# CONNECTOR_A.net
KiCad netlist of a schematic drawn in Altium Designer
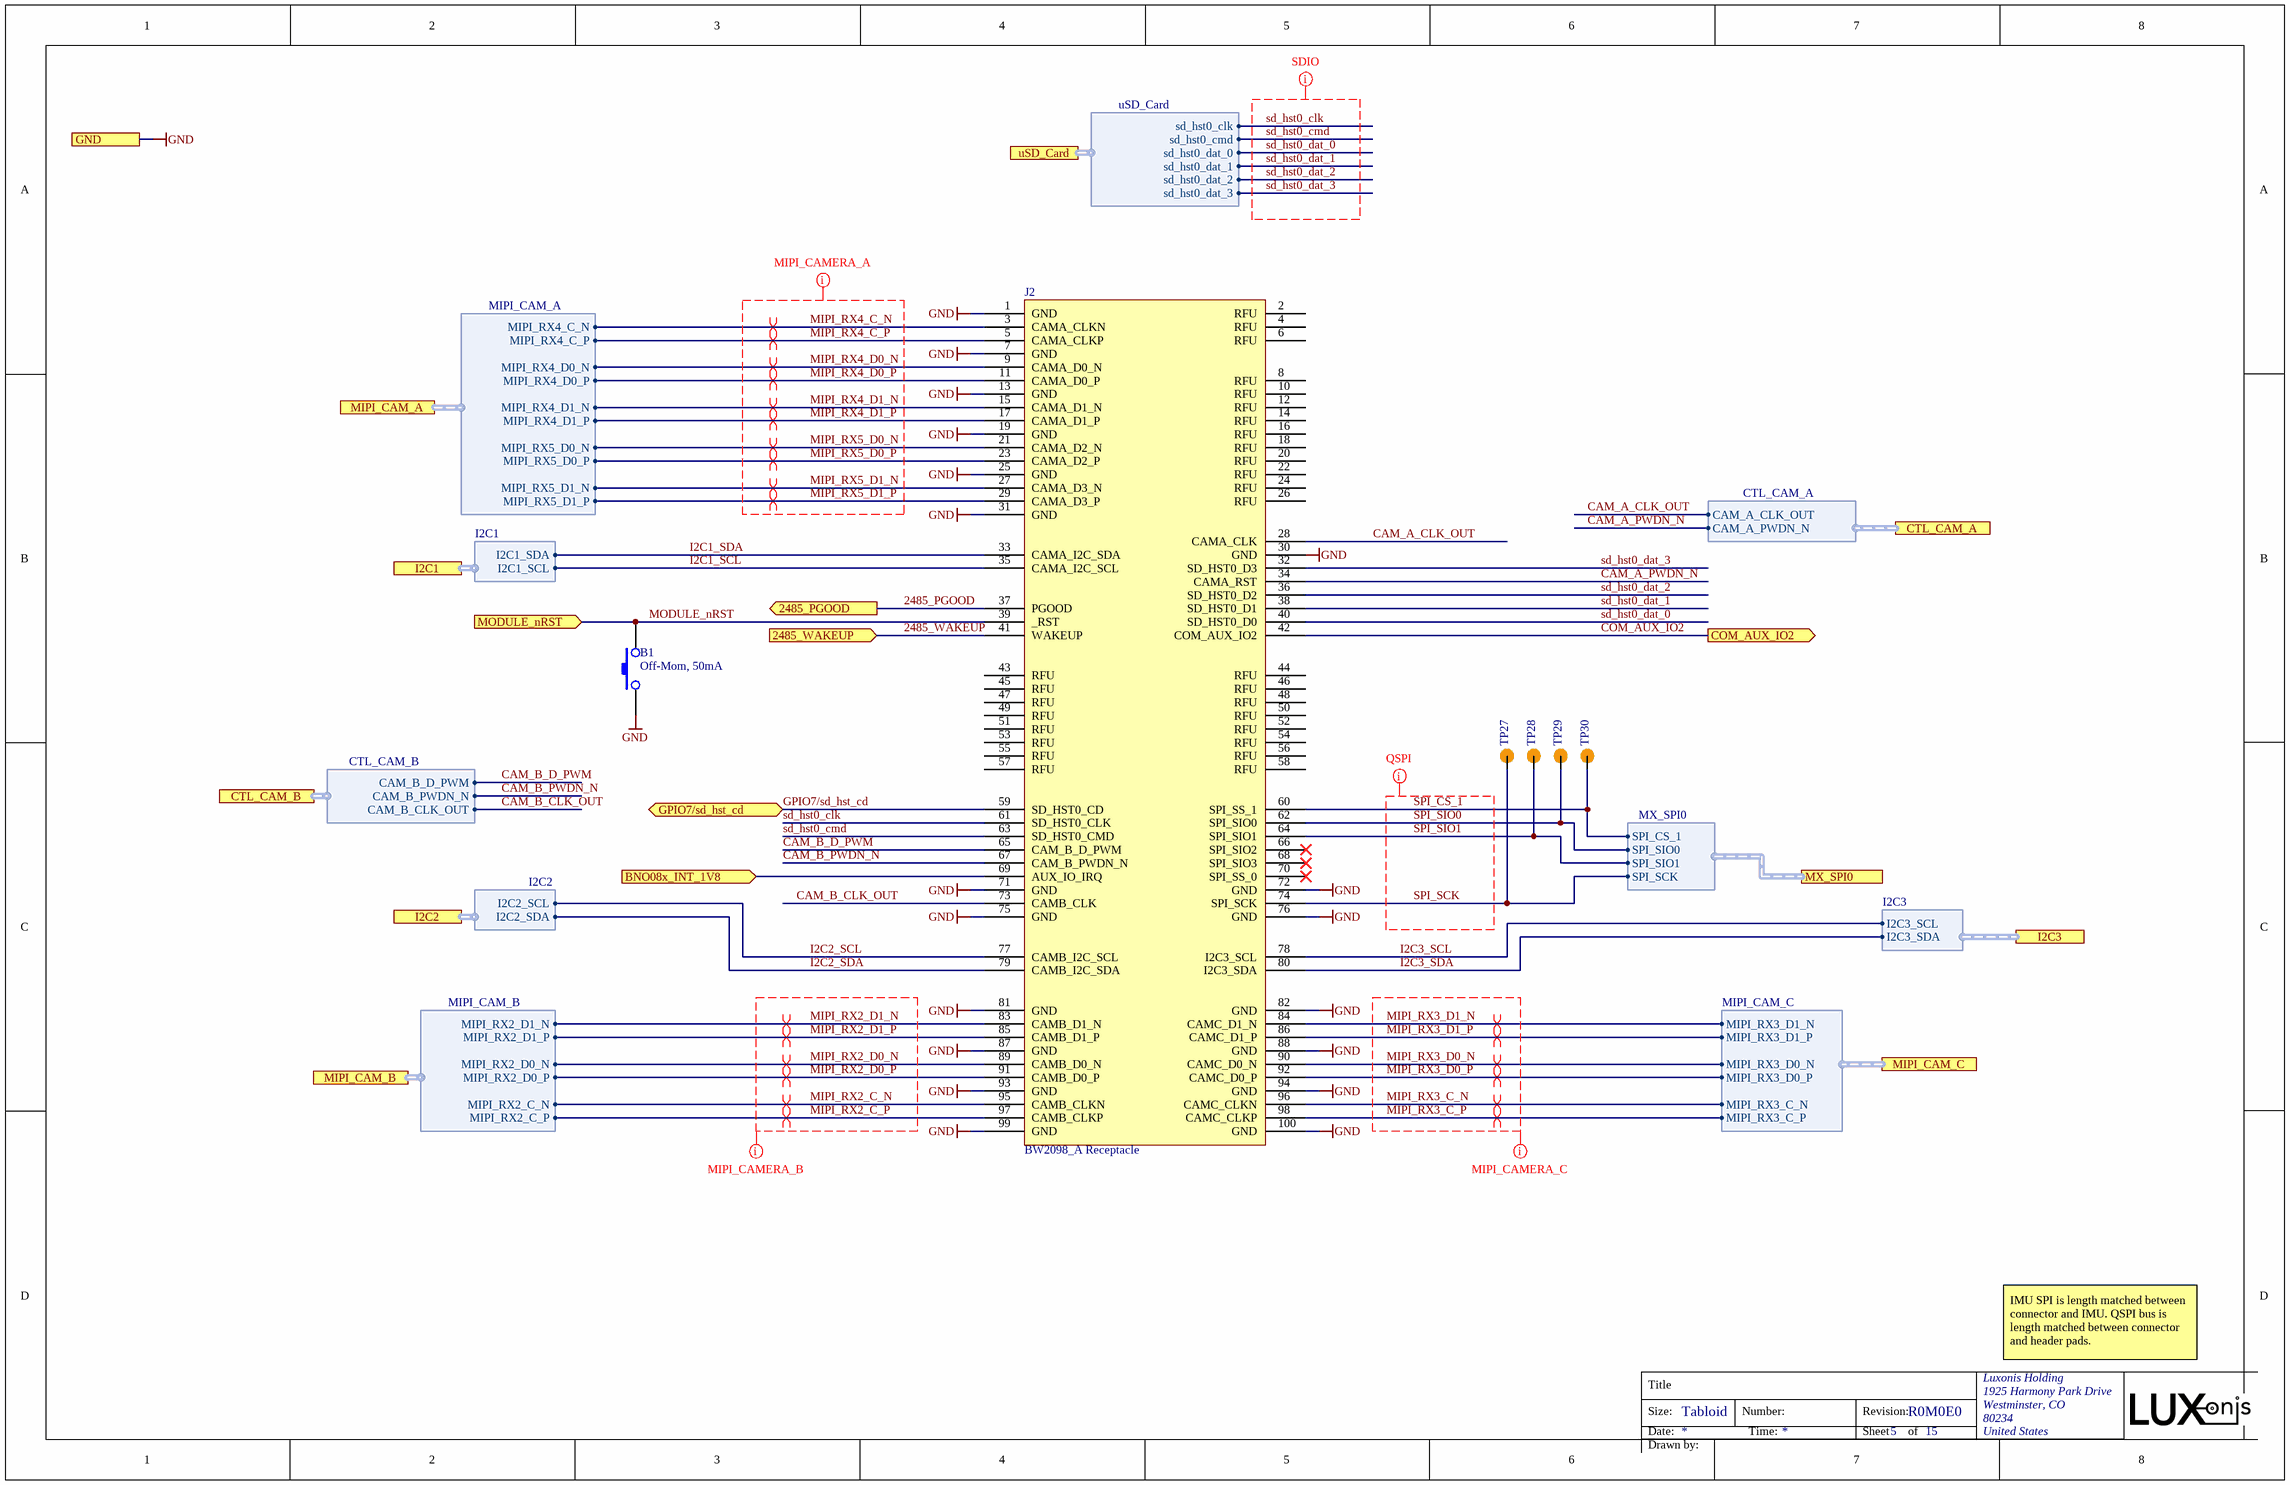
[diagram p0: CONNECTOR_A.SchDoc]

(export (version "E")
  (design (tool "Eeschema 10.0.6"))
  (components
    (comp (ref "B1")
      (value "Off-Mom, 50mA")
      (footprint "LuxonisMaster:DTSM-32N-V")
      (description "SWITCH TACTILE SMT 3.5mm * 6mm , brown 160gf")
      (libsource (lib "LuxonisMaster") (part "DTSM-32N-V"))
    )
    (comp (ref "J2")
      (value "BW2098_A Receptacle")
      (footprint "LuxonisMaster:DF40HC-3.0-100DS-0.4V_minpad")
      (description "CONN RCPT 100POS 0.4MM SMD GOLD BW2098_A Receptacle")
      (libsource (lib "BW2098POE") (part "DF40HC(3.0)-100DS-0.4V_BW2098_A"))
    )
    (comp (ref "TP27")
      (value "TP100_200_NS")
      (footprint "TP100_200_NS")
      (libsource (lib "LuxonisMaster") (part "TEST_POINT"))
    )
    (comp (ref "TP28")
      (value "TP100_200_NS")
      (footprint "TP100_200_NS")
      (libsource (lib "LuxonisMaster") (part "TEST_POINT"))
    )
    (comp (ref "TP29")
      (value "TP100_200_NS")
      (footprint "TP100_200_NS")
      (libsource (lib "LuxonisMaster") (part "TEST_POINT"))
    )
    (comp (ref "TP30")
      (value "TP100_200_NS")
      (footprint "TP100_200_NS")
      (libsource (lib "LuxonisMaster") (part "TEST_POINT"))
    )
  )
  (nets
    (net (code "11") (name "/2485_PGOOD") (class "Default")
      (node (ref "J2") (pin "37") (pinfunction "PGOOD_37") (pintype "passive"))
    )
    (net (code "12") (name "/2485_WAKEUP") (class "Default")
      (node (ref "J2") (pin "41") (pinfunction "WAKEUP_41") (pintype "passive"))
    )
    (net (code "13") (name "/BNO08x_INT_1V8") (class "Default")
      (node (ref "J2") (pin "69") (pinfunction "AUX_IO_IRQ_69") (pintype "passive"))
    )
    (net (code "14") (name "/CAM_A_CLK_OUT") (class "Default")
      (node (ref "J2") (pin "28") (pinfunction "CAMA_CLK_28") (pintype "passive"))
    )
    (net (code "15") (name "/CAM_A_PWDN_N") (class "Default")
      (node (ref "J2") (pin "34") (pinfunction "CAMA_RST_34") (pintype "passive"))
    )
    (net (code "16") (name "/CAM_B_CLK_OUT") (class "Default")
      (node (ref "J2") (pin "73") (pinfunction "CAMB_CLK_73") (pintype "passive"))
    )
    (net (code "17") (name "/CAM_B_D_PWM") (class "Default")
      (node (ref "J2") (pin "65") (pinfunction "CAM_B_D_PWM_65") (pintype "passive"))
    )
    (net (code "18") (name "/CAM_B_PWDN_N") (class "Default")
      (node (ref "J2") (pin "67") (pinfunction "CAM_B_PWDN_N_67") (pintype "passive"))
    )
    (net (code "19") (name "/COM_AUX_IO2") (class "Default")
      (node (ref "J2") (pin "42") (pinfunction "COM_AUX_IO2_42") (pintype "passive"))
    )
    (net (code "20") (name "/GPIO7{slash}sd_hst_cd") (class "Default")
      (node (ref "J2") (pin "59") (pinfunction "SD_HST0_CD_59") (pintype "passive"))
    )
    (net (code "21") (name "/I2C1_SCL") (class "Default")
      (node (ref "J2") (pin "35") (pinfunction "CAMA_I2C_SCL_35") (pintype "passive"))
    )
    (net (code "22") (name "/I2C1_SDA") (class "Default")
      (node (ref "J2") (pin "33") (pinfunction "CAMA_I2C_SDA_33") (pintype "passive"))
    )
    (net (code "23") (name "/I2C2_SCL") (class "Default")
      (node (ref "J2") (pin "77") (pinfunction "CAMB_I2C_SCL_77") (pintype "passive"))
    )
    (net (code "24") (name "/I2C2_SDA") (class "Default")
      (node (ref "J2") (pin "79") (pinfunction "CAMB_I2C_SDA_79") (pintype "passive"))
    )
    (net (code "25") (name "/I2C3_SCL") (class "Default")
      (node (ref "J2") (pin "78") (pinfunction "I2C3_SCL_78") (pintype "passive"))
    )
    (net (code "26") (name "/I2C3_SDA") (class "Default")
      (node (ref "J2") (pin "80") (pinfunction "I2C3_SDA_80") (pintype "passive"))
    )
    (net (code "27") (name "/MIPI_RX2_C_N") (class "Default")
      (node (ref "J2") (pin "95") (pinfunction "CAMB_CLKN_95") (pintype "passive"))
    )
    (net (code "28") (name "/MIPI_RX2_C_P") (class "Default")
      (node (ref "J2") (pin "97") (pinfunction "CAMB_CLKP_97") (pintype "passive"))
    )
    (net (code "29") (name "/MIPI_RX2_D0_N") (class "Default")
      (node (ref "J2") (pin "89") (pinfunction "CAMB_D0_N_89") (pintype "passive"))
    )
    (net (code "30") (name "/MIPI_RX2_D0_P") (class "Default")
      (node (ref "J2") (pin "91") (pinfunction "CAMB_D0_P_91") (pintype "passive"))
    )
    (net (code "31") (name "/MIPI_RX2_D1_N") (class "Default")
      (node (ref "J2") (pin "83") (pinfunction "CAMB_D1_N_83") (pintype "passive"))
    )
    (net (code "32") (name "/MIPI_RX2_D1_P") (class "Default")
      (node (ref "J2") (pin "85") (pinfunction "CAMB_D1_P_85") (pintype "passive"))
    )
    (net (code "33") (name "/MIPI_RX3_C_N") (class "Default")
      (node (ref "J2") (pin "96") (pinfunction "CAMC_CLKN_96") (pintype "passive"))
    )
    (net (code "34") (name "/MIPI_RX3_C_P") (class "Default")
      (node (ref "J2") (pin "98") (pinfunction "CAMC_CLKP_98") (pintype "passive"))
    )
    (net (code "35") (name "/MIPI_RX3_D0_N") (class "Default")
      (node (ref "J2") (pin "90") (pinfunction "CAMC_D0_N_90") (pintype "passive"))
    )
    (net (code "36") (name "/MIPI_RX3_D0_P") (class "Default")
      (node (ref "J2") (pin "92") (pinfunction "CAMC_D0_P_92") (pintype "passive"))
    )
    (net (code "37") (name "/MIPI_RX3_D1_N") (class "Default")
      (node (ref "J2") (pin "84") (pinfunction "CAMC_D1_N_84") (pintype "passive"))
    )
    (net (code "38") (name "/MIPI_RX3_D1_P") (class "Default")
      (node (ref "J2") (pin "86") (pinfunction "CAMC_D1_P_86") (pintype "passive"))
    )
    (net (code "39") (name "/MIPI_RX4_C_N") (class "Default")
      (node (ref "J2") (pin "3") (pinfunction "CAMA_CLKN_3") (pintype "passive"))
    )
    (net (code "40") (name "/MIPI_RX4_C_P") (class "Default")
      (node (ref "J2") (pin "5") (pinfunction "CAMA_CLKP_5") (pintype "passive"))
    )
    (net (code "41") (name "/MIPI_RX4_D0_N") (class "Default")
      (node (ref "J2") (pin "9") (pinfunction "CAMA_D0_N_9") (pintype "passive"))
    )
    (net (code "42") (name "/MIPI_RX4_D0_P") (class "Default")
      (node (ref "J2") (pin "11") (pinfunction "CAMA_D0_P_11") (pintype "passive"))
    )
    (net (code "43") (name "/MIPI_RX4_D1_N") (class "Default")
      (node (ref "J2") (pin "15") (pinfunction "CAMA_D1_N_15") (pintype "passive"))
    )
    (net (code "44") (name "/MIPI_RX4_D1_P") (class "Default")
      (node (ref "J2") (pin "17") (pinfunction "CAMA_D1_P_17") (pintype "passive"))
    )
    (net (code "45") (name "/MIPI_RX5_D0_N") (class "Default")
      (node (ref "J2") (pin "21") (pinfunction "CAMA_D2_N_21") (pintype "passive"))
    )
    (net (code "46") (name "/MIPI_RX5_D0_P") (class "Default")
      (node (ref "J2") (pin "23") (pinfunction "CAMA_D2_P_23") (pintype "passive"))
    )
    (net (code "47") (name "/MIPI_RX5_D1_N") (class "Default")
      (node (ref "J2") (pin "27") (pinfunction "CAMA_D3_N_27") (pintype "passive"))
    )
    (net (code "48") (name "/MIPI_RX5_D1_P") (class "Default")
      (node (ref "J2") (pin "29") (pinfunction "CAMA_D3_P_29") (pintype "passive"))
    )
    (net (code "49") (name "/MODULE_nRST") (class "Default")
      (node (ref "B1") (pin "2") (pinfunction "2_2") (pintype "passive"))
      (node (ref "J2") (pin "39") (pinfunction "_RST_39") (pintype "passive"))
    )
    (net (code "50") (name "/SPI_CS_1") (class "Default")
      (node (ref "J2") (pin "60") (pinfunction "SPI_SS_1_60") (pintype "passive"))
      (node (ref "TP30") (pin "1") (pintype "passive"))
    )
    (net (code "51") (name "/SPI_SCK") (class "Default")
      (node (ref "J2") (pin "74") (pinfunction "SPI_SCK_74") (pintype "passive"))
      (node (ref "TP27") (pin "1") (pintype "passive"))
    )
    (net (code "52") (name "/SPI_SIO0") (class "Default")
      (node (ref "J2") (pin "62") (pinfunction "SPI_SIO0_62") (pintype "passive"))
      (node (ref "TP29") (pin "1") (pintype "passive"))
    )
    (net (code "53") (name "/SPI_SIO1") (class "Default")
      (node (ref "J2") (pin "64") (pinfunction "SPI_SIO1_64") (pintype "passive"))
      (node (ref "TP28") (pin "1") (pintype "passive"))
    )
    (net (code "54") (name "/sd_hst0_clk") (class "Default")
      (node (ref "J2") (pin "61") (pinfunction "SD_HST0_CLK_61") (pintype "passive"))
    )
    (net (code "55") (name "/sd_hst0_cmd") (class "Default")
      (node (ref "J2") (pin "63") (pinfunction "SD_HST0_CMD_63") (pintype "passive"))
    )
    (net (code "56") (name "/sd_hst0_dat_0") (class "Default")
      (node (ref "J2") (pin "40") (pinfunction "SD_HST0_D0_40") (pintype "passive"))
    )
    (net (code "57") (name "/sd_hst0_dat_1") (class "Default")
      (node (ref "J2") (pin "38") (pinfunction "SD_HST0_D1_38") (pintype "passive"))
    )
    (net (code "58") (name "/sd_hst0_dat_2") (class "Default")
      (node (ref "J2") (pin "36") (pinfunction "SD_HST0_D2_36") (pintype "passive"))
    )
    (net (code "59") (name "/sd_hst0_dat_3") (class "Default")
      (node (ref "J2") (pin "32") (pinfunction "SD_HST0_D3_32") (pintype "passive"))
    )
    (net (code "70") (name "GND") (class "Default")
      (node (ref "B1") (pin "1") (pinfunction "1_1") (pintype "passive"))
      (node (ref "J2") (pin "1") (pinfunction "GND_1") (pintype "passive"))
      (node (ref "J2") (pin "100") (pinfunction "GND_100") (pintype "passive"))
      (node (ref "J2") (pin "13") (pinfunction "GND_13") (pintype "passive"))
      (node (ref "J2") (pin "19") (pinfunction "GND_19") (pintype "passive"))
      (node (ref "J2") (pin "25") (pinfunction "GND_25") (pintype "passive"))
      (node (ref "J2") (pin "30") (pinfunction "GND_30") (pintype "passive"))
      (node (ref "J2") (pin "31") (pinfunction "GND_31") (pintype "passive"))
      (node (ref "J2") (pin "7") (pinfunction "GND_7") (pintype "passive"))
      (node (ref "J2") (pin "71") (pinfunction "GND_71") (pintype "passive"))
      (node (ref "J2") (pin "72") (pinfunction "GND_72") (pintype "passive"))
      (node (ref "J2") (pin "75") (pinfunction "GND_75") (pintype "passive"))
      (node (ref "J2") (pin "76") (pinfunction "GND_76") (pintype "passive"))
      (node (ref "J2") (pin "81") (pinfunction "GND_81") (pintype "passive"))
      (node (ref "J2") (pin "82") (pinfunction "GND_82") (pintype "passive"))
      (node (ref "J2") (pin "87") (pinfunction "GND_87") (pintype "passive"))
      (node (ref "J2") (pin "88") (pinfunction "GND_88") (pintype "passive"))
      (node (ref "J2") (pin "93") (pinfunction "GND_93") (pintype "passive"))
      (node (ref "J2") (pin "94") (pinfunction "GND_94") (pintype "passive"))
      (node (ref "J2") (pin "99") (pinfunction "GND_99") (pintype "passive"))
    )
    (net (code "71") (name "unconnected-(J2-RFU-Pad2)") (class "Default")
      (node (ref "J2") (pin "2") (pinfunction "RFU_2") (pintype "passive"))
    )
    (net (code "72") (name "unconnected-(J2-RFU-Pad4)") (class "Default")
      (node (ref "J2") (pin "4") (pinfunction "RFU_4") (pintype "passive"))
    )
    (net (code "73") (name "unconnected-(J2-RFU-Pad6)") (class "Default")
      (node (ref "J2") (pin "6") (pinfunction "RFU_6") (pintype "passive"))
    )
    (net (code "74") (name "unconnected-(J2-RFU-Pad8)") (class "Default")
      (node (ref "J2") (pin "8") (pinfunction "RFU_8") (pintype "passive"))
    )
    (net (code "75") (name "unconnected-(J2-RFU-Pad10)") (class "Default")
      (node (ref "J2") (pin "10") (pinfunction "RFU_10") (pintype "passive"))
    )
    (net (code "76") (name "unconnected-(J2-RFU-Pad12)") (class "Default")
      (node (ref "J2") (pin "12") (pinfunction "RFU_12") (pintype "passive"))
    )
    (net (code "77") (name "unconnected-(J2-RFU-Pad14)") (class "Default")
      (node (ref "J2") (pin "14") (pinfunction "RFU_14") (pintype "passive"))
    )
    (net (code "78") (name "unconnected-(J2-RFU-Pad16)") (class "Default")
      (node (ref "J2") (pin "16") (pinfunction "RFU_16") (pintype "passive"))
    )
    (net (code "79") (name "unconnected-(J2-RFU-Pad18)") (class "Default")
      (node (ref "J2") (pin "18") (pinfunction "RFU_18") (pintype "passive"))
    )
    (net (code "80") (name "unconnected-(J2-RFU-Pad20)") (class "Default")
      (node (ref "J2") (pin "20") (pinfunction "RFU_20") (pintype "passive"))
    )
    (net (code "81") (name "unconnected-(J2-RFU-Pad22)") (class "Default")
      (node (ref "J2") (pin "22") (pinfunction "RFU_22") (pintype "passive"))
    )
    (net (code "82") (name "unconnected-(J2-RFU-Pad24)") (class "Default")
      (node (ref "J2") (pin "24") (pinfunction "RFU_24") (pintype "passive"))
    )
    (net (code "83") (name "unconnected-(J2-RFU-Pad26)") (class "Default")
      (node (ref "J2") (pin "26") (pinfunction "RFU_26") (pintype "passive"))
    )
    (net (code "84") (name "unconnected-(J2-RFU-Pad43)") (class "Default")
      (node (ref "J2") (pin "43") (pinfunction "RFU_43") (pintype "passive"))
    )
    (net (code "85") (name "unconnected-(J2-RFU-Pad44)") (class "Default")
      (node (ref "J2") (pin "44") (pinfunction "RFU_44") (pintype "passive"))
    )
    (net (code "86") (name "unconnected-(J2-RFU-Pad45)") (class "Default")
      (node (ref "J2") (pin "45") (pinfunction "RFU_45") (pintype "passive"))
    )
    (net (code "87") (name "unconnected-(J2-RFU-Pad46)") (class "Default")
      (node (ref "J2") (pin "46") (pinfunction "RFU_46") (pintype "passive"))
    )
    (net (code "88") (name "unconnected-(J2-RFU-Pad47)") (class "Default")
      (node (ref "J2") (pin "47") (pinfunction "RFU_47") (pintype "passive"))
    )
    (net (code "89") (name "unconnected-(J2-RFU-Pad48)") (class "Default")
      (node (ref "J2") (pin "48") (pinfunction "RFU_48") (pintype "passive"))
    )
    (net (code "90") (name "unconnected-(J2-RFU-Pad49)") (class "Default")
      (node (ref "J2") (pin "49") (pinfunction "RFU_49") (pintype "passive"))
    )
    (net (code "91") (name "unconnected-(J2-RFU-Pad50)") (class "Default")
      (node (ref "J2") (pin "50") (pinfunction "RFU_50") (pintype "passive"))
    )
    (net (code "92") (name "unconnected-(J2-RFU-Pad51)") (class "Default")
      (node (ref "J2") (pin "51") (pinfunction "RFU_51") (pintype "passive"))
    )
    (net (code "93") (name "unconnected-(J2-RFU-Pad52)") (class "Default")
      (node (ref "J2") (pin "52") (pinfunction "RFU_52") (pintype "passive"))
    )
    (net (code "94") (name "unconnected-(J2-RFU-Pad53)") (class "Default")
      (node (ref "J2") (pin "53") (pinfunction "RFU_53") (pintype "passive"))
    )
    (net (code "95") (name "unconnected-(J2-RFU-Pad54)") (class "Default")
      (node (ref "J2") (pin "54") (pinfunction "RFU_54") (pintype "passive"))
    )
    (net (code "96") (name "unconnected-(J2-RFU-Pad55)") (class "Default")
      (node (ref "J2") (pin "55") (pinfunction "RFU_55") (pintype "passive"))
    )
    (net (code "97") (name "unconnected-(J2-RFU-Pad56)") (class "Default")
      (node (ref "J2") (pin "56") (pinfunction "RFU_56") (pintype "passive"))
    )
    (net (code "98") (name "unconnected-(J2-RFU-Pad57)") (class "Default")
      (node (ref "J2") (pin "57") (pinfunction "RFU_57") (pintype "passive"))
    )
    (net (code "99") (name "unconnected-(J2-RFU-Pad58)") (class "Default")
      (node (ref "J2") (pin "58") (pinfunction "RFU_58") (pintype "passive"))
    )
    (net (code "100") (name "unconnected-(J2-SPI_SIO2-Pad66)") (class "Default")
      (node (ref "J2") (pin "66") (pinfunction "SPI_SIO2_66") (pintype "passive+no_connect"))
    )
    (net (code "101") (name "unconnected-(J2-SPI_SIO3-Pad68)") (class "Default")
      (node (ref "J2") (pin "68") (pinfunction "SPI_SIO3_68") (pintype "passive+no_connect"))
    )
    (net (code "102") (name "unconnected-(J2-SPI_SS_0-Pad70)") (class "Default")
      (node (ref "J2") (pin "70") (pinfunction "SPI_SS_0_70") (pintype "passive+no_connect"))
    )
  )
)
